# ST1S14.net
KiCad netlist of a schematic drawn in EAGLE
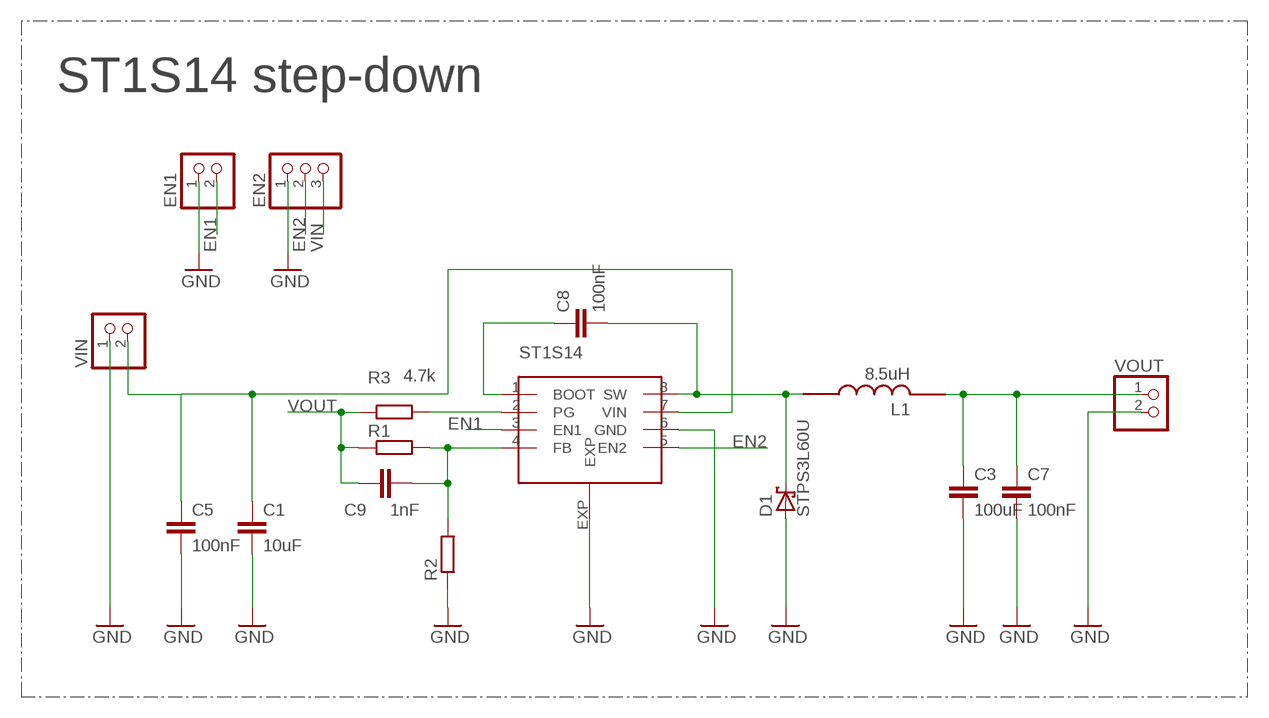
[diagram p0: schematic, sheet 1]

(export (version "E")
  (design (tool "Eeschema 10.0.6"))
  (components
    (comp (ref "C1")
      (value "10uF")
      (footprint "eagle-import:C1210K")
      (libsource (lib "eagle-import") (part "C-EUC1210K"))
    )
    (comp (ref "C3")
      (value "100uF")
      (footprint "eagle-import:C1210K")
      (libsource (lib "eagle-import") (part "C-EUC1210K"))
    )
    (comp (ref "C5")
      (value "100nF")
      (footprint "eagle-import:C0603")
      (libsource (lib "eagle-import") (part "C-EUC0603"))
    )
    (comp (ref "C7")
      (value "100nF")
      (footprint "eagle-import:C0603")
      (libsource (lib "eagle-import") (part "C-EUC0603"))
    )
    (comp (ref "C8")
      (value "100nF")
      (footprint "eagle-import:C0603")
      (libsource (lib "eagle-import") (part "C-EUC0603"))
    )
    (comp (ref "C9")
      (value "1nF")
      (footprint "eagle-import:C0603")
      (libsource (lib "eagle-import") (part "C-EUC0603"))
    )
    (comp (ref "D1")
      (value "STPS3L60U")
      (footprint "eagle-import:SMB")
      (fields (field (name "SPICEPREFIX") "D"))
      (libsource (lib "eagle-import") (part "MBRS130LT3"))
    )
    (comp (ref "EN1")
      (value "PINHD-1X2")
      (footprint "eagle-import:1X02")
      (libsource (lib "eagle-import") (part "PINHD-1X2"))
    )
    (comp (ref "EN2")
      (value "PINHD-1X3")
      (footprint "eagle-import:1X03")
      (libsource (lib "eagle-import") (part "PINHD-1X3"))
    )
    (comp (ref "L1")
      (value "8.5uH")
      (footprint "eagle-import:COIL1")
      (libsource (lib "eagle-import") (part "COIL8.5"))
    )
    (comp (ref "R1")
      (value "R-EU_R0603")
      (footprint "eagle-import:R0603")
      (libsource (lib "eagle-import") (part "R-EU_R0603"))
    )
    (comp (ref "R2")
      (value "R-EU_R0603")
      (footprint "eagle-import:R0603")
      (libsource (lib "eagle-import") (part "R-EU_R0603"))
    )
    (comp (ref "R3")
      (value "4.7k")
      (footprint "eagle-import:R0603")
      (libsource (lib "eagle-import") (part "R-EU_R0603"))
    )
    (comp (ref "U$1")
      (value "ST1S14")
      (footprint "eagle-import:HSOP8")
      (libsource (lib "eagle-import") (part "ST1S14"))
    )
    (comp (ref "VIN")
      (value "PINHD-1X2")
      (footprint "eagle-import:1X02")
      (libsource (lib "eagle-import") (part "PINHD-1X2"))
    )
    (comp (ref "VOUT")
      (value "PINHD-1X2")
      (footprint "eagle-import:1X02")
      (libsource (lib "eagle-import") (part "PINHD-1X2"))
    )
  )
  (nets
    (net (code "1") (name "/EN1") (class "Default")
      (node (ref "EN1") (pin "2") (pinfunction "2_2") (pintype "passive"))
      (node (ref "U$1") (pin "3") (pinfunction "EN1_3") (pintype "bidirectional"))
    )
    (net (code "2") (name "/EN2") (class "Default")
      (node (ref "EN2") (pin "2") (pinfunction "2_2") (pintype "passive"))
      (node (ref "U$1") (pin "5") (pinfunction "EN2_5") (pintype "bidirectional"))
    )
    (net (code "3") (name "/VIN") (class "Default")
      (node (ref "C1") (pin "1") (pinfunction "1_1") (pintype "passive"))
      (node (ref "C5") (pin "1") (pinfunction "1_1") (pintype "passive"))
      (node (ref "EN2") (pin "3") (pinfunction "3_3") (pintype "passive"))
      (node (ref "U$1") (pin "7") (pinfunction "VIN_7") (pintype "bidirectional"))
      (node (ref "VIN") (pin "2") (pinfunction "2_2") (pintype "passive"))
    )
    (net (code "4") (name "/VOUT") (class "Default")
      (node (ref "C3") (pin "1") (pinfunction "1_1") (pintype "passive"))
      (node (ref "C7") (pin "1") (pinfunction "1_1") (pintype "passive"))
      (node (ref "C9") (pin "1") (pinfunction "1_1") (pintype "passive"))
      (node (ref "L1") (pin "2") (pinfunction "2_2") (pintype "passive"))
      (node (ref "R1") (pin "1") (pinfunction "1_1") (pintype "passive"))
      (node (ref "R3") (pin "1") (pinfunction "1_1") (pintype "passive"))
      (node (ref "VOUT") (pin "1") (pinfunction "1_1") (pintype "passive"))
    )
    (net (code "5") (name "GND") (class "Default")
      (node (ref "C1") (pin "2") (pinfunction "2_2") (pintype "passive"))
      (node (ref "C3") (pin "2") (pinfunction "2_2") (pintype "passive"))
      (node (ref "C5") (pin "2") (pinfunction "2_2") (pintype "passive"))
      (node (ref "C7") (pin "2") (pinfunction "2_2") (pintype "passive"))
      (node (ref "D1") (pin "A") (pinfunction "A_A") (pintype "passive"))
      (node (ref "EN1") (pin "1") (pinfunction "1_1") (pintype "passive"))
      (node (ref "EN2") (pin "1") (pinfunction "1_1") (pintype "passive"))
      (node (ref "R2") (pin "1") (pinfunction "1_1") (pintype "passive"))
      (node (ref "U$1") (pin "6") (pinfunction "GND_6") (pintype "bidirectional"))
      (node (ref "U$1") (pin "EXP") (pinfunction "EXP_EXP") (pintype "bidirectional"))
      (node (ref "VIN") (pin "1") (pinfunction "1_1") (pintype "passive"))
      (node (ref "VOUT") (pin "2") (pinfunction "2_2") (pintype "passive"))
    )
    (net (code "6") (name "Net-(U$1-BOOT)") (class "Default")
      (node (ref "C8") (pin "1") (pinfunction "1_1") (pintype "passive"))
      (node (ref "U$1") (pin "1") (pinfunction "BOOT_1") (pintype "bidirectional"))
    )
    (net (code "7") (name "Net-(U$1-FB)") (class "Default")
      (node (ref "C9") (pin "2") (pinfunction "2_2") (pintype "passive"))
      (node (ref "R1") (pin "2") (pinfunction "2_2") (pintype "passive"))
      (node (ref "R2") (pin "2") (pinfunction "2_2") (pintype "passive"))
      (node (ref "U$1") (pin "4") (pinfunction "FB_4") (pintype "bidirectional"))
    )
    (net (code "8") (name "Net-(U$1-PG)") (class "Default")
      (node (ref "R3") (pin "2") (pinfunction "2_2") (pintype "passive"))
      (node (ref "U$1") (pin "2") (pinfunction "PG_2") (pintype "bidirectional"))
    )
    (net (code "9") (name "Net-(U$1-SW)") (class "Default")
      (node (ref "C8") (pin "2") (pinfunction "2_2") (pintype "passive"))
      (node (ref "D1") (pin "C") (pinfunction "C_C") (pintype "passive"))
      (node (ref "L1") (pin "1") (pinfunction "1_1") (pintype "passive"))
      (node (ref "U$1") (pin "8") (pinfunction "SW_8") (pintype "bidirectional"))
    )
  )
)
